# MCU.net
KiCad netlist of a schematic drawn in Altium Designer
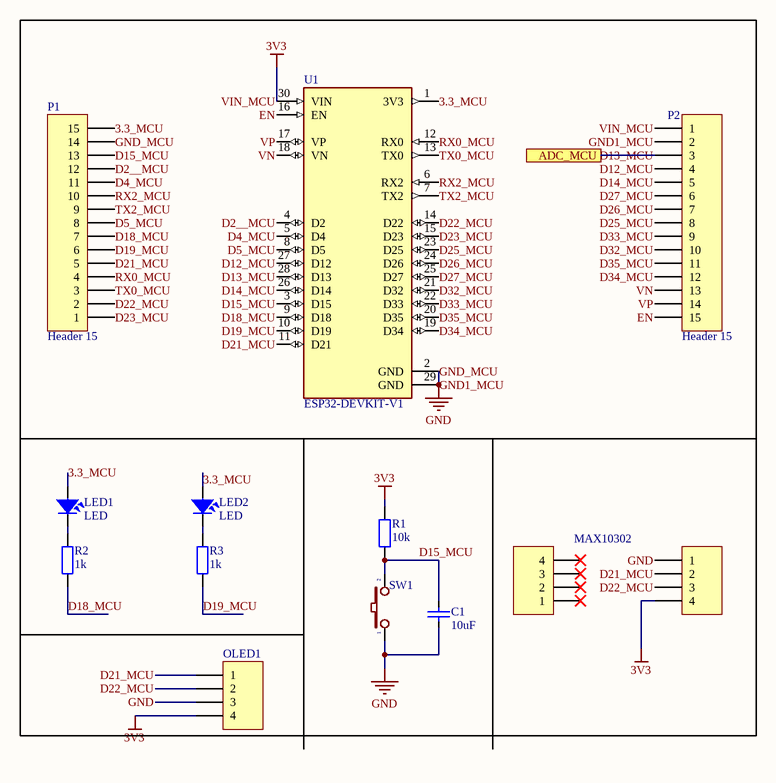
[diagram p0: MCU.SchDoc]

(export (version "E")
  (design (tool "Eeschema 10.0.6"))
  (components
    (comp (ref "C1")
      (value "10uF")
      (footprint "CAP_0805")
      (description "Capacitor")
      (fields (field (name "PUBLISHER") "Altium Limited"))
      (libsource (lib "My Library") (part "CapSMD"))
    )
    (comp (ref "LED1")
      (value "LED")
      (footprint "LED-0805-Blue")
      (description "LED Single colour Green and Red")
      (libsource (lib "My Library") (part "LED"))
    )
    (comp (ref "LED2")
      (value "LED")
      (footprint "LED-0805-Blue")
      (description "LED Single colour Green and Red")
      (libsource (lib "My Library") (part "LED"))
    )
    (comp (ref "MAX10302")
      (value "Header 4")
      (footprint "HDR1X4")
      (description "Header, 4-Pin")
      (fields (field (name "PUBLISHER") "Altium Limited"))
      (libsource (lib "My Library") (part "Header 4"))
    )
    (comp (ref "OLED1")
      (value "LCD")
      (footprint "HDR1X4")
      (description "Header, 4-Pin")
      (fields (field (name "PUBLISHER") "Altium Limited"))
      (libsource (lib "My Library") (part "Header 4"))
    )
    (comp (ref "P1")
      (value "Header 15")
      (footprint "HDR1X15")
      (description "Header, 15-Pin")
      (fields (field (name "PUBLISHER") "Altium Limited"))
      (libsource (lib "My Library") (part "Header 15"))
    )
    (comp (ref "P2")
      (value "Header 15")
      (footprint "HDR1X15")
      (description "Header, 15-Pin")
      (fields (field (name "PUBLISHER") "Altium Limited"))
      (libsource (lib "") (part "Header 15_1"))
    )
    (comp (ref "P3")
      (value "Header 4")
      (footprint "HDR1X4")
      (description "Header, 4-Pin")
      (fields (field (name "PUBLISHER") "Altium Limited"))
      (libsource (lib "") (part "Header 4_1"))
    )
    (comp (ref "R1")
      (value "10k")
      (footprint "RES-SMD-0805")
      (description "Resistor SMD")
      (fields
        (field (name "MANUFACTURER") "Generic Components")
        (field (name "PUBLISHER") "Altium Hobart Technology Centre")
      )
      (libsource (lib "My Library") (part "Resistor - SMD"))
    )
    (comp (ref "R2")
      (value "1k")
      (footprint "RES-SMD-0805")
      (description "Resistor SMD")
      (fields
        (field (name "MANUFACTURER") "Generic Components")
        (field (name "PUBLISHER") "Altium Hobart Technology Centre")
      )
      (libsource (lib "My Library") (part "Resistor - SMD"))
    )
    (comp (ref "R3")
      (value "1k")
      (footprint "RES-SMD-0805")
      (description "Resistor SMD")
      (fields
        (field (name "MANUFACTURER") "Generic Components")
        (field (name "PUBLISHER") "Altium Hobart Technology Centre")
      )
      (libsource (lib "My Library") (part "Resistor - SMD"))
    )
    (comp (ref "SW1")
      (value "SW")
      (footprint "SW2")
      (description "Switch button 2 pin")
      (libsource (lib "My Library") (part "SW2"))
    )
    (comp (ref "U1")
      (value "ESP32-DEVKIT-V1")
      (footprint "MODULE_ESP32_DEVKIT_V1")
      (fields (field (name "MF") "Do it"))
      (libsource (lib "ESP32-DEVKIT-V1") (part "ESP32-DEVKIT-V1"))
    )
  )
  (nets
    (net (code "1") (name "/3.3_MCU") (class "Default")
      (node (ref "LED1") (pin "1") (pinfunction "1_1") (pintype "passive"))
      (node (ref "LED2") (pin "1") (pinfunction "1_1") (pintype "passive"))
      (node (ref "P1") (pin "15") (pinfunction "15_15") (pintype "passive"))
      (node (ref "U1") (pin "1") (pinfunction "3V3_1") (pintype "output"))
    )
    (net (code "2") (name "/D2__MCU") (class "Default")
      (node (ref "P1") (pin "12") (pinfunction "12_12") (pintype "passive"))
      (node (ref "U1") (pin "4") (pinfunction "D2_4") (pintype "bidirectional"))
    )
    (net (code "3") (name "/D4_MCU") (class "Default")
      (node (ref "P1") (pin "11") (pinfunction "11_11") (pintype "passive"))
      (node (ref "U1") (pin "5") (pinfunction "D4_5") (pintype "bidirectional"))
    )
    (net (code "4") (name "/D5_MCU") (class "Default")
      (node (ref "P1") (pin "8") (pinfunction "8_8") (pintype "passive"))
      (node (ref "U1") (pin "8") (pinfunction "D5_8") (pintype "bidirectional"))
    )
    (net (code "5") (name "/D12_MCU") (class "Default")
      (node (ref "P2") (pin "4") (pinfunction "4_4") (pintype "passive"))
      (node (ref "U1") (pin "27") (pinfunction "D12_27") (pintype "bidirectional"))
    )
    (net (code "6") (name "/D13_MCU") (class "Default")
      (node (ref "P2") (pin "3") (pinfunction "3_3") (pintype "passive"))
      (node (ref "U1") (pin "28") (pinfunction "D13_28") (pintype "bidirectional"))
    )
    (net (code "7") (name "/D14_MCU") (class "Default")
      (node (ref "P2") (pin "5") (pinfunction "5_5") (pintype "passive"))
      (node (ref "U1") (pin "26") (pinfunction "D14_26") (pintype "bidirectional"))
    )
    (net (code "8") (name "/D15_MCU") (class "Default")
      (node (ref "C1") (pin "2") (pinfunction "2_2") (pintype "passive"))
      (node (ref "P1") (pin "13") (pinfunction "13_13") (pintype "passive"))
      (node (ref "R1") (pin "2") (pinfunction "2_2") (pintype "passive"))
      (node (ref "SW1") (pin "2") (pinfunction "2_2") (pintype "passive"))
      (node (ref "U1") (pin "3") (pinfunction "D15_3") (pintype "bidirectional"))
    )
    (net (code "9") (name "/D18_MCU") (class "Default")
      (node (ref "P1") (pin "7") (pinfunction "7_7") (pintype "passive"))
      (node (ref "R2") (pin "2") (pinfunction "2_2") (pintype "passive"))
      (node (ref "U1") (pin "9") (pinfunction "D18_9") (pintype "bidirectional"))
    )
    (net (code "10") (name "/D19_MCU") (class "Default")
      (node (ref "P1") (pin "6") (pinfunction "6_6") (pintype "passive"))
      (node (ref "R3") (pin "2") (pinfunction "2_2") (pintype "passive"))
      (node (ref "U1") (pin "10") (pinfunction "D19_10") (pintype "bidirectional"))
    )
    (net (code "11") (name "/D21_MCU") (class "Default")
      (node (ref "MAX10302") (pin "2") (pinfunction "2_2") (pintype "passive"))
      (node (ref "OLED1") (pin "1") (pinfunction "1_1") (pintype "passive"))
      (node (ref "P1") (pin "5") (pinfunction "5_5") (pintype "passive"))
      (node (ref "U1") (pin "11") (pinfunction "D21_11") (pintype "bidirectional"))
    )
    (net (code "12") (name "/D22_MCU") (class "Default")
      (node (ref "MAX10302") (pin "3") (pinfunction "3_3") (pintype "passive"))
      (node (ref "OLED1") (pin "2") (pinfunction "2_2") (pintype "passive"))
      (node (ref "P1") (pin "2") (pinfunction "2_2") (pintype "passive"))
      (node (ref "U1") (pin "14") (pinfunction "D22_14") (pintype "bidirectional"))
    )
    (net (code "13") (name "/D23_MCU") (class "Default")
      (node (ref "P1") (pin "1") (pinfunction "1_1") (pintype "passive"))
      (node (ref "U1") (pin "15") (pinfunction "D23_15") (pintype "bidirectional"))
    )
    (net (code "14") (name "/D25_MCU") (class "Default")
      (node (ref "P2") (pin "8") (pinfunction "8_8") (pintype "passive"))
      (node (ref "U1") (pin "23") (pinfunction "D25_23") (pintype "bidirectional"))
    )
    (net (code "15") (name "/D26_MCU") (class "Default")
      (node (ref "P2") (pin "7") (pinfunction "7_7") (pintype "passive"))
      (node (ref "U1") (pin "24") (pinfunction "D26_24") (pintype "bidirectional"))
    )
    (net (code "16") (name "/D27_MCU") (class "Default")
      (node (ref "P2") (pin "6") (pinfunction "6_6") (pintype "passive"))
      (node (ref "U1") (pin "25") (pinfunction "D27_25") (pintype "bidirectional"))
    )
    (net (code "17") (name "/D32_MCU") (class "Default")
      (node (ref "P2") (pin "10") (pinfunction "10_10") (pintype "passive"))
      (node (ref "U1") (pin "21") (pinfunction "D32_21") (pintype "bidirectional"))
    )
    (net (code "18") (name "/D33_MCU") (class "Default")
      (node (ref "P2") (pin "9") (pinfunction "9_9") (pintype "passive"))
      (node (ref "U1") (pin "22") (pinfunction "D33_22") (pintype "bidirectional"))
    )
    (net (code "19") (name "/D34_MCU") (class "Default")
      (node (ref "P2") (pin "12") (pinfunction "12_12") (pintype "passive"))
      (node (ref "U1") (pin "19") (pinfunction "D34_19") (pintype "bidirectional"))
    )
    (net (code "20") (name "/D35_MCU") (class "Default")
      (node (ref "P2") (pin "11") (pinfunction "11_11") (pintype "passive"))
      (node (ref "U1") (pin "20") (pinfunction "D35_20") (pintype "bidirectional"))
    )
    (net (code "21") (name "/EN") (class "Default")
      (node (ref "P2") (pin "15") (pinfunction "15_15") (pintype "passive"))
      (node (ref "U1") (pin "16") (pinfunction "EN_16") (pintype "input"))
    )
    (net (code "22") (name "/RX0_MCU") (class "Default")
      (node (ref "P1") (pin "4") (pinfunction "4_4") (pintype "passive"))
      (node (ref "U1") (pin "12") (pinfunction "RX0_12") (pintype "input"))
    )
    (net (code "23") (name "/RX2_MCU") (class "Default")
      (node (ref "P1") (pin "10") (pinfunction "10_10") (pintype "passive"))
      (node (ref "U1") (pin "6") (pinfunction "RX2_6") (pintype "input"))
    )
    (net (code "24") (name "/TX0_MCU") (class "Default")
      (node (ref "P1") (pin "3") (pinfunction "3_3") (pintype "passive"))
      (node (ref "U1") (pin "13") (pinfunction "TX0_13") (pintype "output"))
    )
    (net (code "25") (name "/TX2_MCU") (class "Default")
      (node (ref "P1") (pin "9") (pinfunction "9_9") (pintype "passive"))
      (node (ref "U1") (pin "7") (pinfunction "TX2_7") (pintype "output"))
    )
    (net (code "26") (name "/VN") (class "Default")
      (node (ref "P2") (pin "13") (pinfunction "13_13") (pintype "passive"))
      (node (ref "U1") (pin "18") (pinfunction "VN_18") (pintype "bidirectional"))
    )
    (net (code "27") (name "/VP") (class "Default")
      (node (ref "P2") (pin "14") (pinfunction "14_14") (pintype "passive"))
      (node (ref "U1") (pin "17") (pinfunction "VP_17") (pintype "bidirectional"))
    )
    (net (code "28") (name "3V3") (class "Default")
      (node (ref "MAX10302") (pin "4") (pinfunction "4_4") (pintype "passive"))
      (node (ref "OLED1") (pin "4") (pinfunction "4_4") (pintype "passive"))
      (node (ref "P2") (pin "1") (pinfunction "1_1") (pintype "passive"))
      (node (ref "R1") (pin "1") (pinfunction "1_1") (pintype "passive"))
      (node (ref "U1") (pin "30") (pinfunction "VIN_30") (pintype "input"))
    )
    (net (code "29") (name "GND") (class "Default")
      (node (ref "C1") (pin "1") (pinfunction "1_1") (pintype "passive"))
      (node (ref "MAX10302") (pin "1") (pinfunction "1_1") (pintype "passive"))
      (node (ref "OLED1") (pin "3") (pinfunction "3_3") (pintype "passive"))
      (node (ref "P1") (pin "14") (pinfunction "14_14") (pintype "passive"))
      (node (ref "P2") (pin "2") (pinfunction "2_2") (pintype "passive"))
      (node (ref "SW1") (pin "1") (pinfunction "1_1") (pintype "passive"))
      (node (ref "U1") (pin "2") (pinfunction "GND_2") (pintype "power_in"))
      (node (ref "U1") (pin "29") (pinfunction "GND_29") (pintype "power_in"))
    )
    (net (code "30") (name "Net-(LED1-Pad2)") (class "Default")
      (node (ref "LED1") (pin "2") (pinfunction "2_2") (pintype "passive"))
      (node (ref "R2") (pin "1") (pinfunction "1_1") (pintype "passive"))
    )
    (net (code "31") (name "Net-(LED2-Pad2)") (class "Default")
      (node (ref "LED2") (pin "2") (pinfunction "2_2") (pintype "passive"))
      (node (ref "R3") (pin "1") (pinfunction "1_1") (pintype "passive"))
    )
    (net (code "32") (name "unconnected-(P3-Pad1)") (class "Default")
      (node (ref "P3") (pin "1") (pinfunction "1_1") (pintype "passive+no_connect"))
    )
    (net (code "33") (name "unconnected-(P3-Pad2)") (class "Default")
      (node (ref "P3") (pin "2") (pinfunction "2_2") (pintype "passive+no_connect"))
    )
    (net (code "34") (name "unconnected-(P3-Pad3)") (class "Default")
      (node (ref "P3") (pin "3") (pinfunction "3_3") (pintype "passive+no_connect"))
    )
    (net (code "35") (name "unconnected-(P3-Pad4)") (class "Default")
      (node (ref "P3") (pin "4") (pinfunction "4_4") (pintype "passive+no_connect"))
    )
  )
)
